# EFR32_IO.net
KiCad netlist of a schematic drawn in Altium Designer
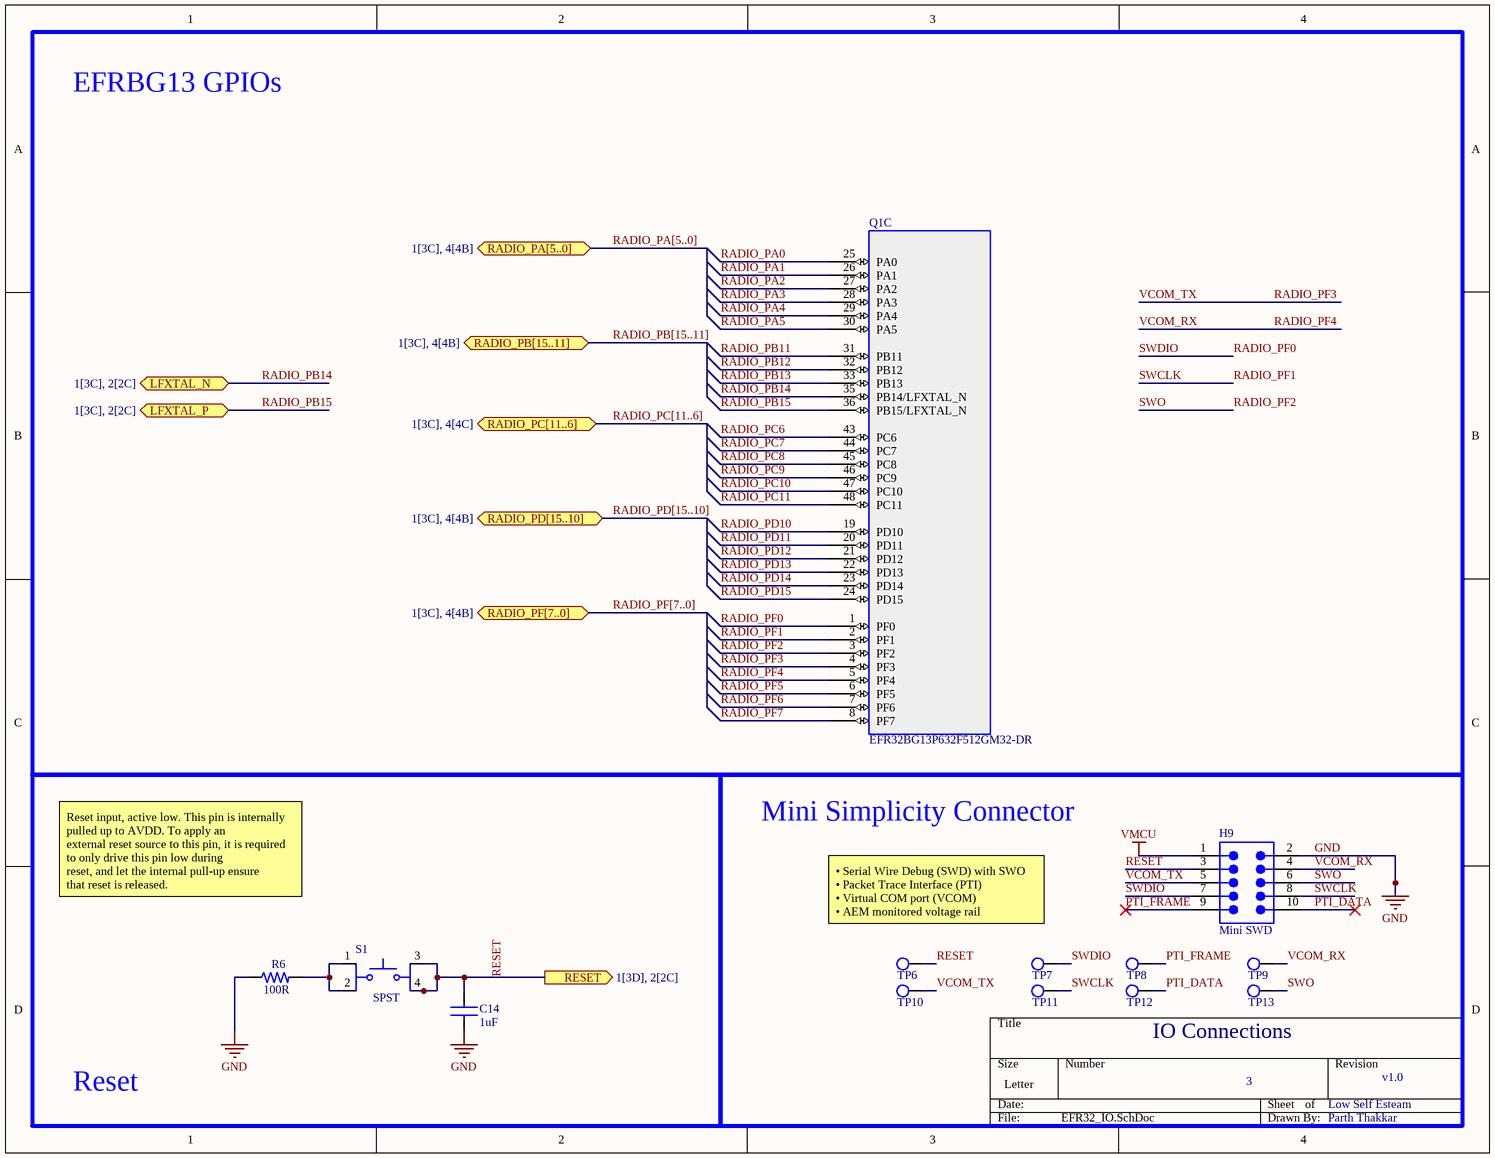
[diagram p0:  EFR32_IO.SchDoc]

(export (version "E")
  (design (tool "Eeschema 10.0.6"))
  (components
    (comp (ref "C14")
      (value "1uF")
      (footprint "Capacitor 0603")
      (fields
        (field (name "MANUFACTURER") "Murata")
        (field (name "MANUFACTURER PART NUMBER") "GRM188R61A105KA61D")
        (field (name "Comment") "CAP 1uF 10V 0603")
      )
      (libsource (lib "Keyboard_parts") (part "CAP 1uF 10V 0603"))
    )
    (comp (ref "H9")
      (value "Mini SWD")
      (footprint "Mini Simplicity Connector")
      (description "Mini SWD 0.05\" Pitch Connector - 10 Pin SMT Box Header")
      (fields
        (field (name "MANUFACTURER") "Adafruit Industries")
        (field (name "MANUFACTURER PART NUMBER") "4048")
      )
      (libsource (lib "Keyboard_parts") (part "Debug Connector Mini SWD - 0.05{dblquote}"))
    )
    (comp (ref "Q1")
      (value "EFR32BG13P632F512GM32-DR")
      (footprint "EFR32BG")
      (description "BLue Gecko")
      (fields (field (name "MANUFACTURER") "Silicon Labs"))
      (libsource (lib "Keyboard_parts") (part "EFR32BG13P632F512GM32-DR"))
    )
    (comp (ref "R6")
      (value "100R")
      (footprint "Resistor 0603")
      (fields
        (field (name "MANUFACTURER") "Yageo")
        (field (name "MANUFACTURER PART NUMBER") "RC0603FR-07100RL")
        (field (name "TOLERANCE") "1%")
      )
      (libsource (lib "Keyboard_parts") (part "RES 100R 0603"))
    )
    (comp (ref "S1")
      (value "SPST")
      (footprint "SPST")
      (fields
        (field (name "MANUFACTURER") "E-Switch")
        (field (name "MANUFACTURER PART NUMBER") "TL3301NF260QG")
      )
      (libsource (lib "Keyboard_parts") (part "SPST"))
    )
    (comp (ref "TP6")
      (value "Test point")
      (footprint "Test Point")
      (libsource (lib "Keyboard_parts") (part "Test point"))
    )
    (comp (ref "TP7")
      (value "Test point")
      (footprint "Test Point")
      (libsource (lib "Keyboard_parts") (part "Test point"))
    )
    (comp (ref "TP8")
      (value "Test point")
      (footprint "Test Point")
      (libsource (lib "Keyboard_parts") (part "Test point"))
    )
    (comp (ref "TP9")
      (value "Test point")
      (footprint "Test Point")
      (libsource (lib "Keyboard_parts") (part "Test point"))
    )
    (comp (ref "TP10")
      (value "Test point")
      (footprint "Test Point")
      (libsource (lib "Keyboard_parts") (part "Test point"))
    )
    (comp (ref "TP11")
      (value "Test point")
      (footprint "Test Point")
      (libsource (lib "Keyboard_parts") (part "Test point"))
    )
    (comp (ref "TP12")
      (value "Test point")
      (footprint "Test Point")
      (libsource (lib "Keyboard_parts") (part "Test point"))
    )
    (comp (ref "TP13")
      (value "Test point")
      (footprint "Test Point")
      (libsource (lib "Keyboard_parts") (part "Test point"))
    )
  )
  (nets
    (net (code "1") (name "/PTI_DATA") (class "Default")
      (node (ref "H9") (pin "10") (pinfunction "10_10") (pintype "passive"))
      (node (ref "TP12") (pin "1") (pinfunction "1_1") (pintype "passive"))
    )
    (net (code "2") (name "/PTI_FRAME") (class "Default")
      (node (ref "H9") (pin "9") (pinfunction "9_9") (pintype "passive"))
      (node (ref "TP8") (pin "1") (pinfunction "1_1") (pintype "passive"))
    )
    (net (code "3") (name "/RADIO_PA0") (class "Default")
      (node (ref "Q1") (pin "25") (pinfunction "PA0_25") (pintype "bidirectional"))
    )
    (net (code "4") (name "/RADIO_PA1") (class "Default")
      (node (ref "Q1") (pin "26") (pinfunction "PA1_26") (pintype "bidirectional"))
    )
    (net (code "5") (name "/RADIO_PA2") (class "Default")
      (node (ref "Q1") (pin "27") (pinfunction "PA2_27") (pintype "bidirectional"))
    )
    (net (code "6") (name "/RADIO_PA3") (class "Default")
      (node (ref "Q1") (pin "28") (pinfunction "PA3_28") (pintype "bidirectional"))
    )
    (net (code "7") (name "/RADIO_PA4") (class "Default")
      (node (ref "Q1") (pin "29") (pinfunction "PA4_29") (pintype "bidirectional"))
    )
    (net (code "8") (name "/RADIO_PA5") (class "Default")
      (node (ref "Q1") (pin "30") (pinfunction "PA5_30") (pintype "bidirectional"))
    )
    (net (code "10") (name "/RADIO_PB11") (class "Default")
      (node (ref "Q1") (pin "31") (pinfunction "PB11_31") (pintype "bidirectional"))
    )
    (net (code "11") (name "/RADIO_PB12") (class "Default")
      (node (ref "Q1") (pin "32") (pinfunction "PB12_32") (pintype "bidirectional"))
    )
    (net (code "12") (name "/RADIO_PB13") (class "Default")
      (node (ref "Q1") (pin "33") (pinfunction "PB13_33") (pintype "bidirectional"))
    )
    (net (code "13") (name "/RADIO_PB14") (class "Default")
      (node (ref "Q1") (pin "35") (pinfunction "PB14/LFXTAL_N_35") (pintype "bidirectional"))
    )
    (net (code "14") (name "/RADIO_PB15") (class "Default")
      (node (ref "Q1") (pin "36") (pinfunction "PB15/LFXTAL_N_36") (pintype "bidirectional"))
    )
    (net (code "16") (name "/RADIO_PC6") (class "Default")
      (node (ref "Q1") (pin "43") (pinfunction "PC6_43") (pintype "bidirectional"))
    )
    (net (code "17") (name "/RADIO_PC7") (class "Default")
      (node (ref "Q1") (pin "44") (pinfunction "PC7_44") (pintype "bidirectional"))
    )
    (net (code "18") (name "/RADIO_PC8") (class "Default")
      (node (ref "Q1") (pin "45") (pinfunction "PC8_45") (pintype "bidirectional"))
    )
    (net (code "19") (name "/RADIO_PC9") (class "Default")
      (node (ref "Q1") (pin "46") (pinfunction "PC9_46") (pintype "bidirectional"))
    )
    (net (code "20") (name "/RADIO_PC10") (class "Default")
      (node (ref "Q1") (pin "47") (pinfunction "PC10_47") (pintype "bidirectional"))
    )
    (net (code "21") (name "/RADIO_PC11") (class "Default")
      (node (ref "Q1") (pin "48") (pinfunction "PC11_48") (pintype "bidirectional"))
    )
    (net (code "23") (name "/RADIO_PD10") (class "Default")
      (node (ref "Q1") (pin "19") (pinfunction "PD10_19") (pintype "bidirectional"))
    )
    (net (code "24") (name "/RADIO_PD11") (class "Default")
      (node (ref "Q1") (pin "20") (pinfunction "PD11_20") (pintype "bidirectional"))
    )
    (net (code "25") (name "/RADIO_PD12") (class "Default")
      (node (ref "Q1") (pin "21") (pinfunction "PD12_21") (pintype "bidirectional"))
    )
    (net (code "26") (name "/RADIO_PD13") (class "Default")
      (node (ref "Q1") (pin "22") (pinfunction "PD13_22") (pintype "bidirectional"))
    )
    (net (code "27") (name "/RADIO_PD14") (class "Default")
      (node (ref "Q1") (pin "23") (pinfunction "PD14_23") (pintype "bidirectional"))
    )
    (net (code "28") (name "/RADIO_PD15") (class "Default")
      (node (ref "Q1") (pin "24") (pinfunction "PD15_24") (pintype "bidirectional"))
    )
    (net (code "30") (name "/RADIO_PF0") (class "Default")
      (node (ref "H9") (pin "7") (pinfunction "7_7") (pintype "passive"))
      (node (ref "Q1") (pin "1") (pinfunction "PF0_1") (pintype "bidirectional"))
      (node (ref "TP7") (pin "1") (pinfunction "1_1") (pintype "passive"))
    )
    (net (code "31") (name "/RADIO_PF1") (class "Default")
      (node (ref "H9") (pin "8") (pinfunction "8_8") (pintype "passive"))
      (node (ref "Q1") (pin "2") (pinfunction "PF1_2") (pintype "bidirectional"))
      (node (ref "TP11") (pin "1") (pinfunction "1_1") (pintype "passive"))
    )
    (net (code "32") (name "/RADIO_PF2") (class "Default")
      (node (ref "H9") (pin "6") (pinfunction "6_6") (pintype "passive"))
      (node (ref "Q1") (pin "3") (pinfunction "PF2_3") (pintype "bidirectional"))
      (node (ref "TP13") (pin "1") (pinfunction "1_1") (pintype "passive"))
    )
    (net (code "33") (name "/RADIO_PF3") (class "Default")
      (node (ref "H9") (pin "5") (pinfunction "5_5") (pintype "passive"))
      (node (ref "Q1") (pin "4") (pinfunction "PF3_4") (pintype "bidirectional"))
      (node (ref "TP10") (pin "1") (pinfunction "1_1") (pintype "passive"))
    )
    (net (code "34") (name "/RADIO_PF4") (class "Default")
      (node (ref "H9") (pin "4") (pinfunction "4_4") (pintype "passive"))
      (node (ref "Q1") (pin "5") (pinfunction "PF4_5") (pintype "bidirectional"))
      (node (ref "TP9") (pin "1") (pinfunction "1_1") (pintype "passive"))
    )
    (net (code "35") (name "/RADIO_PF5") (class "Default")
      (node (ref "Q1") (pin "6") (pinfunction "PF5_6") (pintype "bidirectional"))
    )
    (net (code "36") (name "/RADIO_PF6") (class "Default")
      (node (ref "Q1") (pin "7") (pinfunction "PF6_7") (pintype "bidirectional"))
    )
    (net (code "37") (name "/RADIO_PF7") (class "Default")
      (node (ref "Q1") (pin "8") (pinfunction "PF7_8") (pintype "bidirectional"))
    )
    (net (code "39") (name "/RESET") (class "Default")
      (node (ref "C14") (pin "1") (pinfunction "1_1") (pintype "passive"))
      (node (ref "H9") (pin "3") (pinfunction "3_3") (pintype "passive"))
      (node (ref "S1") (pin "3") (pinfunction "3_3") (pintype "passive"))
      (node (ref "S1") (pin "4") (pinfunction "4_4") (pintype "passive"))
      (node (ref "TP6") (pin "1") (pinfunction "1_1") (pintype "passive"))
    )
    (net (code "40") (name "GND") (class "Default")
      (node (ref "C14") (pin "2") (pinfunction "2_2") (pintype "passive"))
      (node (ref "H9") (pin "2") (pinfunction "2_2") (pintype "passive"))
      (node (ref "R6") (pin "1") (pinfunction "1_1") (pintype "passive"))
    )
    (net (code "41") (name "Net-(R6-Pad2)") (class "Default")
      (node (ref "R6") (pin "2") (pinfunction "2_2") (pintype "passive"))
      (node (ref "S1") (pin "1") (pinfunction "1_1") (pintype "passive"))
      (node (ref "S1") (pin "2") (pinfunction "2_2") (pintype "passive"))
    )
    (net (code "42") (name "VMCU") (class "Default")
      (node (ref "H9") (pin "1") (pinfunction "1_1") (pintype "passive"))
    )
  )
)
